# buffers_5bits.net
KiCad netlist of a schematic drawn in Altium Designer
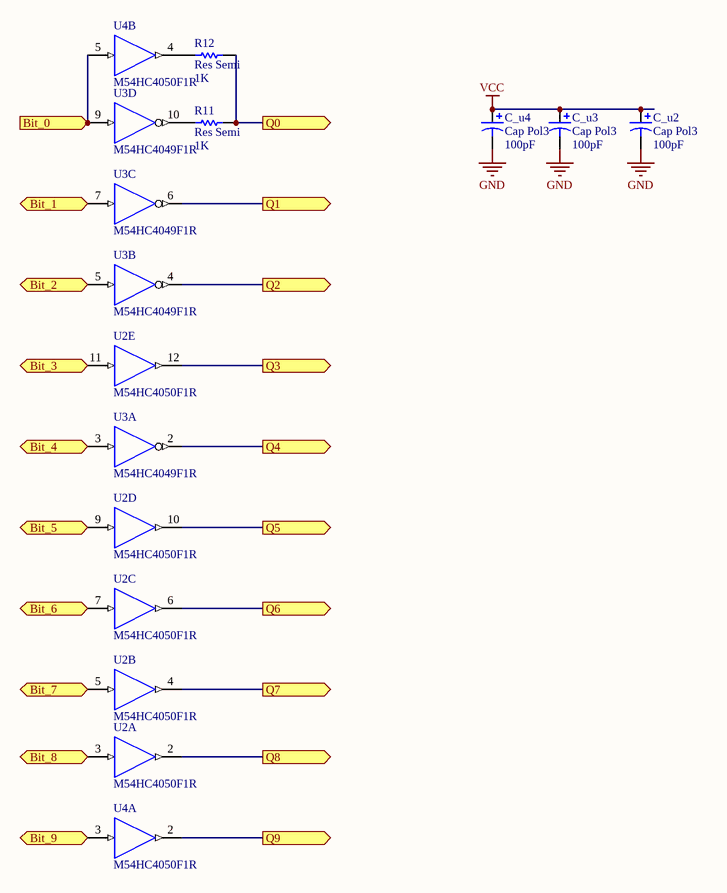
[diagram p0: buffers_5bits.SchDoc]

(export (version "E")
  (design (tool "Eeschema 10.0.6"))
  (components
    (comp (ref "C_u2")
      (value "Cap Pol3")
      (footprint "C0805")
      (description "Polarized Capacitor (Surface Mount)")
      (fields (field (name "ALTIUM_VALUE") "100pF") (field (name "PUBLISHER") "Altium Limited"))
      (libsource (lib "Miscellaneous Devices") (part "Cap Pol3"))
    )
    (comp (ref "C_u3")
      (value "Cap Pol3")
      (footprint "C0805")
      (description "Polarized Capacitor (Surface Mount)")
      (fields (field (name "ALTIUM_VALUE") "100pF") (field (name "PUBLISHER") "Altium Limited"))
      (libsource (lib "Miscellaneous Devices") (part "Cap Pol3"))
    )
    (comp (ref "C_u4")
      (value "Cap Pol3")
      (footprint "C0805")
      (description "Polarized Capacitor (Surface Mount)")
      (fields (field (name "ALTIUM_VALUE") "100pF") (field (name "PUBLISHER") "Altium Limited"))
      (libsource (lib "Miscellaneous Devices") (part "Cap Pol3"))
    )
    (comp (ref "R11")
      (value "Res Semi")
      (footprint "2012[0805]")
      (description "Semiconductor Resistor")
      (fields (field (name "ALTIUM_VALUE") "1K") (field (name "PUBLISHER") "Altium Limited"))
      (libsource (lib "Miscellaneous Devices") (part "Res Semi"))
    )
    (comp (ref "R12")
      (value "Res Semi")
      (footprint "2012[0805]")
      (description "Semiconductor Resistor")
      (fields (field (name "ALTIUM_VALUE") "1K") (field (name "PUBLISHER") "Altium Limited"))
      (libsource (lib "Miscellaneous Devices") (part "Res Semi"))
    )
    (comp (ref "U2")
      (value "M54HC4050F1R")
      (footprint "DIP16")
      (description "Hex Buffer/Converter Non-Inverting")
      (fields (field (name "PUBLISHER") "Altium Limited"))
      (libsource (lib "ST Logic Gate") (part "M54HC4050F1R"))
    )
    (comp (ref "U3")
      (value "M54HC4049F1R")
      (footprint "DIP16")
      (description "Hex Buffer/Converter Invertering")
      (fields (field (name "PUBLISHER") "Altium Limited"))
      (libsource (lib "ST Logic Gate") (part "M54HC4049F1R"))
    )
    (comp (ref "U4")
      (value "M54HC4050F1R")
      (footprint "DIP16")
      (description "Hex Buffer/Converter Non-Inverting")
      (fields (field (name "PUBLISHER") "Altium Limited"))
      (libsource (lib "ST Logic Gate") (part "M54HC4050F1R"))
    )
  )
  (nets
    (net (code "1") (name "/Bit_0") (class "Default")
      (node (ref "U3") (pin "9") (pinfunction "A_9") (pintype "input"))
      (node (ref "U4") (pin "5") (pinfunction "A_5") (pintype "input"))
    )
    (net (code "2") (name "/Bit_1") (class "Default")
      (node (ref "U3") (pin "7") (pinfunction "A_7") (pintype "input"))
    )
    (net (code "3") (name "/Bit_2") (class "Default")
      (node (ref "U3") (pin "5") (pinfunction "A_5") (pintype "input"))
    )
    (net (code "4") (name "/Bit_3") (class "Default")
      (node (ref "U2") (pin "11") (pinfunction "A_11") (pintype "input"))
    )
    (net (code "5") (name "/Bit_4") (class "Default")
      (node (ref "U3") (pin "3") (pinfunction "A_3") (pintype "input"))
    )
    (net (code "6") (name "/Bit_5") (class "Default")
      (node (ref "U2") (pin "9") (pinfunction "A_9") (pintype "input"))
    )
    (net (code "7") (name "/Bit_6") (class "Default")
      (node (ref "U2") (pin "7") (pinfunction "A_7") (pintype "input"))
    )
    (net (code "8") (name "/Bit_7") (class "Default")
      (node (ref "U2") (pin "5") (pinfunction "A_5") (pintype "input"))
    )
    (net (code "9") (name "/Bit_8") (class "Default")
      (node (ref "U2") (pin "3") (pinfunction "A_3") (pintype "input"))
    )
    (net (code "10") (name "/Bit_9") (class "Default")
      (node (ref "U4") (pin "3") (pinfunction "A_3") (pintype "input"))
    )
    (net (code "11") (name "/Q0") (class "Default")
      (node (ref "R11") (pin "1") (pinfunction "1_1") (pintype "passive"))
      (node (ref "R12") (pin "1") (pinfunction "1_1") (pintype "passive"))
    )
    (net (code "12") (name "/Q1") (class "Default")
      (node (ref "U3") (pin "6") (pinfunction "Y_6") (pintype "output"))
    )
    (net (code "13") (name "/Q2") (class "Default")
      (node (ref "U3") (pin "4") (pinfunction "Y_4") (pintype "output"))
    )
    (net (code "14") (name "/Q3") (class "Default")
      (node (ref "U2") (pin "12") (pinfunction "Y_12") (pintype "output"))
    )
    (net (code "15") (name "/Q4") (class "Default")
      (node (ref "U3") (pin "2") (pinfunction "Y_2") (pintype "output"))
    )
    (net (code "16") (name "/Q5") (class "Default")
      (node (ref "U2") (pin "10") (pinfunction "Y_10") (pintype "output"))
    )
    (net (code "17") (name "/Q6") (class "Default")
      (node (ref "U2") (pin "6") (pinfunction "Y_6") (pintype "output"))
    )
    (net (code "18") (name "/Q7") (class "Default")
      (node (ref "U2") (pin "4") (pinfunction "Y_4") (pintype "output"))
    )
    (net (code "19") (name "/Q8") (class "Default")
      (node (ref "U2") (pin "2") (pinfunction "Y_2") (pintype "output"))
    )
    (net (code "20") (name "/Q9") (class "Default")
      (node (ref "U4") (pin "2") (pinfunction "Y_2") (pintype "output"))
    )
    (net (code "21") (name "GND") (class "Default")
      (node (ref "C_u2") (pin "2") (pinfunction "2_2") (pintype "passive"))
      (node (ref "C_u3") (pin "2") (pinfunction "2_2") (pintype "passive"))
      (node (ref "C_u4") (pin "2") (pinfunction "2_2") (pintype "passive"))
      (node (ref "U2") (pin "8") (pinfunction "GND_8") (pintype "power_in"))
      (node (ref "U3") (pin "8") (pinfunction "GND_8") (pintype "power_in"))
      (node (ref "U4") (pin "8") (pinfunction "GND_8") (pintype "power_in"))
    )
    (net (code "22") (name "Net-(U3D-Y)") (class "Default")
      (node (ref "R11") (pin "2") (pinfunction "2_2") (pintype "passive"))
      (node (ref "U3") (pin "10") (pinfunction "Y_10") (pintype "output"))
    )
    (net (code "23") (name "Net-(U4B-Y)") (class "Default")
      (node (ref "R12") (pin "2") (pinfunction "2_2") (pintype "passive"))
      (node (ref "U4") (pin "4") (pinfunction "Y_4") (pintype "output"))
    )
    (net (code "24") (name "VCC") (class "Default")
      (node (ref "C_u2") (pin "1") (pinfunction "1_1") (pintype "passive"))
      (node (ref "C_u3") (pin "1") (pinfunction "1_1") (pintype "passive"))
      (node (ref "C_u4") (pin "1") (pinfunction "1_1") (pintype "passive"))
      (node (ref "U2") (pin "1") (pinfunction "VCC_1") (pintype "power_in"))
      (node (ref "U3") (pin "1") (pinfunction "VCC_1") (pintype "power_in"))
      (node (ref "U4") (pin "1") (pinfunction "VCC_1") (pintype "power_in"))
    )
  )
)
